# TTFT_3_0.net
KiCad netlist of a schematic drawn in Altium Designer
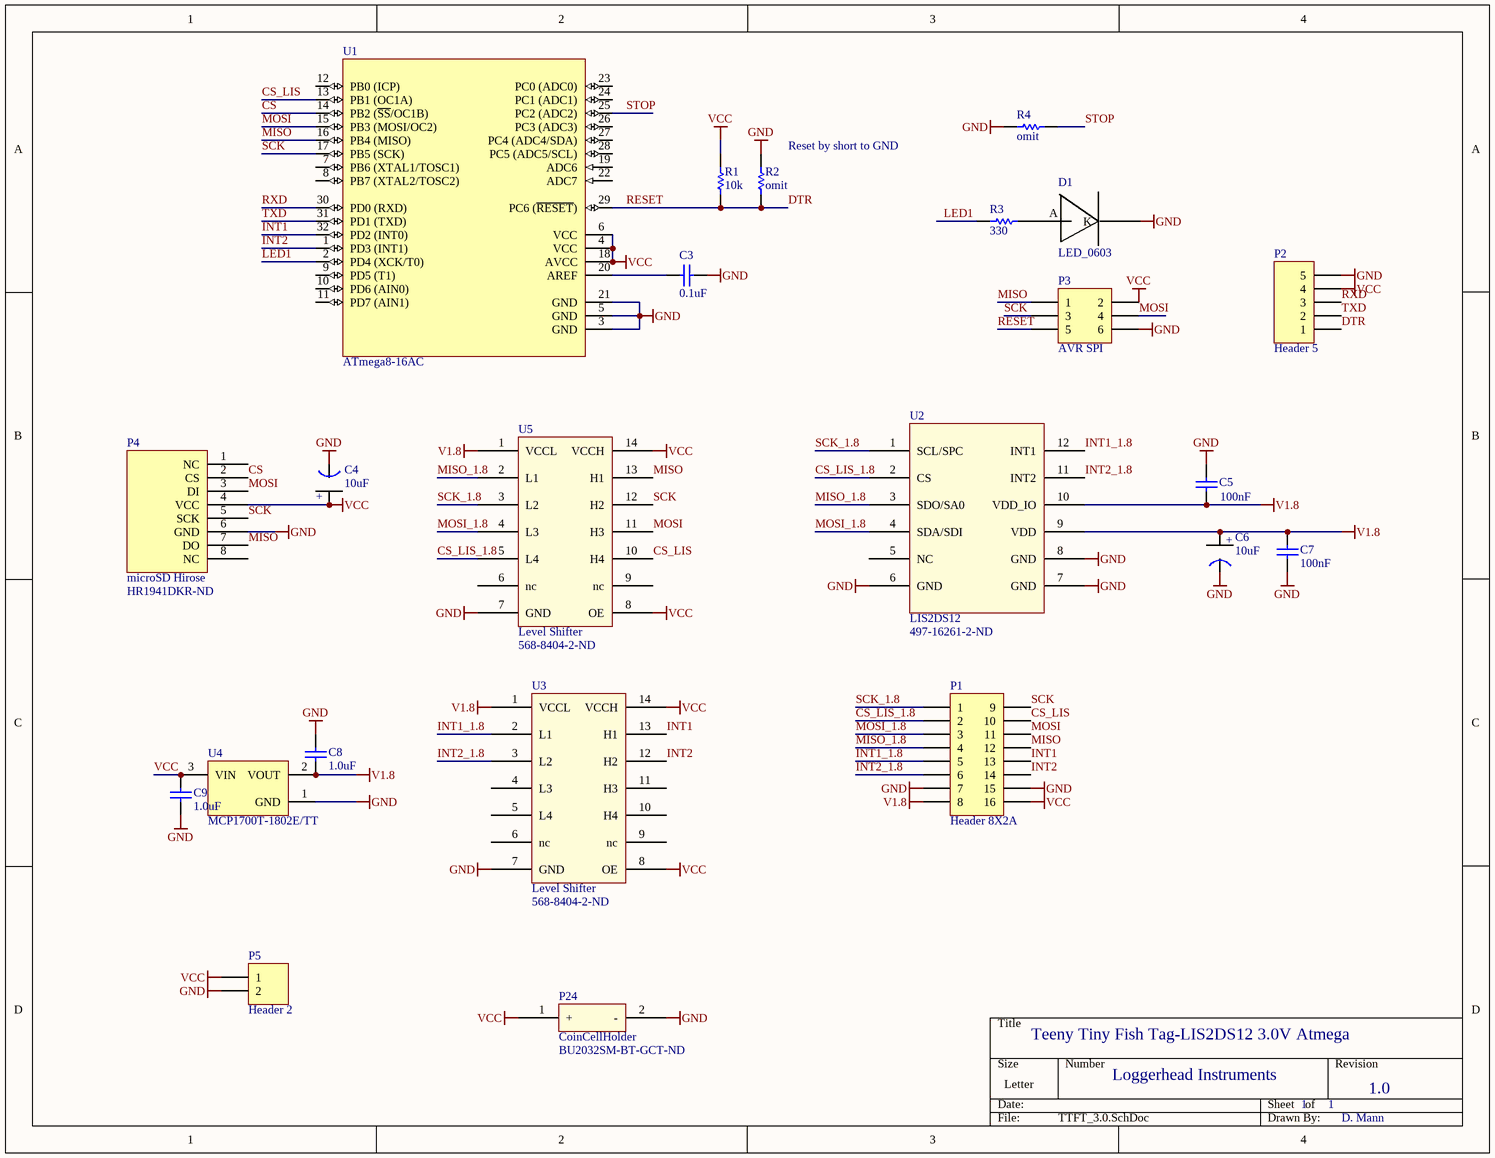
[diagram p0: TTFT_3.0.SchDoc]

(export (version "E")
  (design (tool "Eeschema 10.0.6"))
  (components
    (comp (ref "C3")
      (value "0.1uF")
      (footprint "0402")
      (description "Ceramic Chip Capacitor - Standard")
      (fields (field (name "PUBLISHER") "Altium Limited"))
      (libsource (lib "KEMET Chip Capacitor") (part "C0402"))
    )
    (comp (ref "C4") (value "10uF") (footprint "Tant0805") (libsource (lib "Loggerhead") (part "Tant0805")))
    (comp (ref "C5")
      (value "100nF")
      (footprint "0402")
      (description "Ceramic Chip Capacitor - Standard")
      (fields (field (name "PUBLISHER") "Altium Limited"))
      (libsource (lib "KEMET Chip Capacitor") (part "C0402"))
    )
    (comp (ref "C6") (value "10uF") (footprint "Tant0805") (libsource (lib "Loggerhead") (part "Tant0805")))
    (comp (ref "C7")
      (value "100nF")
      (footprint "0402")
      (description "Ceramic Chip Capacitor - Standard")
      (fields (field (name "PUBLISHER") "Altium Limited"))
      (libsource (lib "KEMET Chip Capacitor") (part "C0402"))
    )
    (comp (ref "C8")
      (value "1.0uF")
      (footprint "0402")
      (description "Ceramic Chip Capacitor - Standard")
      (fields (field (name "PUBLISHER") "Altium Limited"))
      (libsource (lib "KEMET Chip Capacitor") (part "C0402"))
    )
    (comp (ref "C9")
      (value "1.0uF")
      (footprint "0402")
      (description "Ceramic Chip Capacitor - Standard")
      (fields (field (name "PUBLISHER") "Altium Limited"))
      (libsource (lib "KEMET Chip Capacitor") (part "C0402"))
    )
    (comp (ref "D1")
      (value "LED_0603")
      (footprint "Diode0603")
      (libsource (lib "Loggerhead") (part "LED_0603"))
    )
    (comp (ref "P1")
      (value "Header 8X2A")
      (footprint "HDR2X8_CEN")
      (description "Header, 8-Pin, Dual row")
      (fields (field (name "PUBLISHER") "Altium Limited"))
      (libsource (lib "Miscellaneous Connectors") (part "Header 8X2A"))
    )
    (comp (ref "P2")
      (value "Header 5")
      (footprint "HDR1X5")
      (description "Header, 5-Pin")
      (fields (field (name "PUBLISHER") "Altium Limited"))
      (libsource (lib "Miscellaneous Connectors") (part "Header 5"))
    )
    (comp (ref "P3")
      (value "AVR SPI")
      (footprint "HDR2X3")
      (description "Header, 3-Pin, Dual row")
      (fields (field (name "PUBLISHER") "Altium Limited"))
      (libsource (lib "Miscellaneous Connectors") (part "Header 3X2"))
    )
    (comp (ref "P4")
      (value "microSD Hirose")
      (footprint "DM3D microSD")
      (fields (field (name "SUPPLIER PART NUMBER 1") "HR1941DKR-ND"))
      (libsource (lib "Loggerhead") (part "microSD Hirose"))
    )
    (comp (ref "P5")
      (value "Header 2")
      (footprint "HDR1X2")
      (description "Header, 2-Pin")
      (fields (field (name "PUBLISHER") "Altium Limited"))
      (libsource (lib "Miscellaneous Connectors") (part "Header 2"))
    )
    (comp (ref "P24")
      (value "CoinCellHolder")
      (footprint "CoinCellHolder")
      (fields (field (name "SUPPLIER PART NUMBER 1") "BU2032SM-BT-GCT-ND"))
      (libsource (lib "Loggerhead") (part "CoinCellHolder"))
    )
    (comp (ref "R1")
      (value "10k")
      (footprint "3-0603")
      (fields (field (name "PUBLISHER") "Altium Limited"))
      (libsource (lib "Panasonic Resistor") (part "ERJ3RK"))
    )
    (comp (ref "R2")
      (value "omit")
      (footprint "3-0603")
      (fields (field (name "PUBLISHER") "Altium Limited"))
      (libsource (lib "Panasonic Resistor") (part "ERJ3RK"))
    )
    (comp (ref "R3")
      (value "330")
      (footprint "3-0603")
      (fields (field (name "PUBLISHER") "Altium Limited"))
      (libsource (lib "Panasonic Resistor") (part "ERJ3RK"))
    )
    (comp (ref "R4")
      (value "omit")
      (footprint "3-0603")
      (fields (field (name "PUBLISHER") "Altium Limited"))
      (libsource (lib "Panasonic Resistor") (part "ERJ3RK"))
    )
    (comp (ref "U1")
      (value "ATmega8-16AC")
      (footprint "32M1-A_M")
      (description "8-Bit AVR Microcontroller with 8K Bytes of In-System Programmable Flash Memory")
      (fields (field (name "PUBLISHER") "Altium Limited"))
      (libsource (lib "Atmel Microcontroller 8-Bit AVR") (part "ATmega8-16AC"))
    )
    (comp (ref "U2")
      (value "LIS2DS12")
      (footprint "LGA-12")
      (fields (field (name "SUPPLIER PART NUMBER 1") "497-16261-2-ND"))
      (libsource (lib "Loggerhead") (part "LIS2DS12"))
    )
    (comp (ref "U3")
      (value "Level Shifter")
      (footprint "DHVQFN14")
      (description "Voltage level translator")
      (fields (field (name "SUPPLIER PART NUMBER 1") "568-8404-2-ND"))
      (libsource (lib "Loggerhead") (part "NTB0104"))
    )
    (comp (ref "U4")
      (value "MCP1700T-1802E/TT")
      (footprint "SOT-23-TT3_N")
      (description "Low Quiescent Current LDO, 3-Pin SOT-23, Extended Temperature, Tape and Reel")
      (fields (field (name "MANUFACTURER") "Microchip"))
      (libsource (lib "Microchip Power Management Line Regulator") (part "MCP1700T-1802E/TT"))
    )
    (comp (ref "U5")
      (value "Level Shifter")
      (footprint "DHVQFN14")
      (description "Voltage level translator")
      (fields (field (name "SUPPLIER PART NUMBER 1") "568-8404-2-ND"))
      (libsource (lib "Loggerhead") (part "NTB0104"))
    )
  )
  (nets
    (net (code "1") (name "/CS") (class "Default")
      (node (ref "P4") (pin "2") (pinfunction "CS_2") (pintype "passive"))
      (node (ref "U1") (pin "14") (pinfunction "PB2_(~{SS}/OC1B)_14") (pintype "bidirectional"))
    )
    (net (code "2") (name "/CS_LIS") (class "Default")
      (node (ref "P1") (pin "10") (pinfunction "10_10") (pintype "passive"))
      (node (ref "U1") (pin "13") (pinfunction "PB1_(OC1A)_13") (pintype "bidirectional"))
      (node (ref "U5") (pin "10") (pinfunction "H4_10") (pintype "passive"))
    )
    (net (code "3") (name "/CS_LIS_1.8") (class "Default")
      (node (ref "P1") (pin "2") (pinfunction "2_2") (pintype "passive"))
      (node (ref "U2") (pin "2") (pinfunction "CS_2") (pintype "passive"))
      (node (ref "U5") (pin "5") (pinfunction "L4_5") (pintype "passive"))
    )
    (net (code "4") (name "/DTR") (class "Default")
      (node (ref "P2") (pin "1") (pinfunction "1_1") (pintype "passive"))
      (node (ref "P3") (pin "5") (pinfunction "5_5") (pintype "passive"))
      (node (ref "R1") (pin "1") (pinfunction "1_1") (pintype "passive"))
      (node (ref "R2") (pin "1") (pinfunction "1_1") (pintype "passive"))
      (node (ref "U1") (pin "29") (pinfunction "PC6_(~{RESET})_29") (pintype "bidirectional"))
    )
    (net (code "5") (name "/INT1") (class "Default")
      (node (ref "P1") (pin "13") (pinfunction "13_13") (pintype "passive"))
      (node (ref "U1") (pin "32") (pinfunction "PD2_(INT0)_32") (pintype "bidirectional"))
      (node (ref "U3") (pin "13") (pinfunction "H1_13") (pintype "passive"))
    )
    (net (code "6") (name "/INT1_1.8") (class "Default")
      (node (ref "P1") (pin "5") (pinfunction "5_5") (pintype "passive"))
      (node (ref "U2") (pin "12") (pinfunction "INT1_12") (pintype "passive"))
      (node (ref "U3") (pin "2") (pinfunction "L1_2") (pintype "passive"))
    )
    (net (code "7") (name "/INT2") (class "Default")
      (node (ref "P1") (pin "14") (pinfunction "14_14") (pintype "passive"))
      (node (ref "U1") (pin "1") (pinfunction "PD3_(INT1)_1") (pintype "bidirectional"))
      (node (ref "U3") (pin "12") (pinfunction "H2_12") (pintype "passive"))
    )
    (net (code "8") (name "/INT2_1.8") (class "Default")
      (node (ref "P1") (pin "6") (pinfunction "6_6") (pintype "passive"))
      (node (ref "U2") (pin "11") (pinfunction "INT2_11") (pintype "passive"))
      (node (ref "U3") (pin "3") (pinfunction "L2_3") (pintype "passive"))
    )
    (net (code "9") (name "/LED1") (class "Default")
      (node (ref "R3") (pin "1") (pinfunction "1_1") (pintype "passive"))
      (node (ref "U1") (pin "2") (pinfunction "PD4_(XCK/T0)_2") (pintype "bidirectional"))
    )
    (net (code "10") (name "/MISO") (class "Default")
      (node (ref "P1") (pin "12") (pinfunction "12_12") (pintype "passive"))
      (node (ref "P3") (pin "1") (pinfunction "1_1") (pintype "passive"))
      (node (ref "P4") (pin "7") (pinfunction "DO_7") (pintype "passive"))
      (node (ref "U1") (pin "16") (pinfunction "PB4_(MISO)_16") (pintype "bidirectional"))
      (node (ref "U5") (pin "13") (pinfunction "H1_13") (pintype "passive"))
    )
    (net (code "11") (name "/MISO_1.8") (class "Default")
      (node (ref "P1") (pin "4") (pinfunction "4_4") (pintype "passive"))
      (node (ref "U2") (pin "3") (pinfunction "SDO/SA0_3") (pintype "passive"))
      (node (ref "U5") (pin "2") (pinfunction "L1_2") (pintype "passive"))
    )
    (net (code "12") (name "/MOSI") (class "Default")
      (node (ref "P1") (pin "11") (pinfunction "11_11") (pintype "passive"))
      (node (ref "P3") (pin "4") (pinfunction "4_4") (pintype "passive"))
      (node (ref "P4") (pin "3") (pinfunction "DI_3") (pintype "passive"))
      (node (ref "U1") (pin "15") (pinfunction "PB3_(MOSI/OC2)_15") (pintype "bidirectional"))
      (node (ref "U5") (pin "11") (pinfunction "H3_11") (pintype "passive"))
    )
    (net (code "13") (name "/MOSI_1.8") (class "Default")
      (node (ref "P1") (pin "3") (pinfunction "3_3") (pintype "passive"))
      (node (ref "U2") (pin "4") (pinfunction "SDA/SDI_4") (pintype "passive"))
      (node (ref "U5") (pin "4") (pinfunction "L3_4") (pintype "passive"))
    )
    (net (code "14") (name "/RXD") (class "Default")
      (node (ref "P2") (pin "3") (pinfunction "3_3") (pintype "passive"))
      (node (ref "U1") (pin "30") (pinfunction "PD0_(RXD)_30") (pintype "bidirectional"))
    )
    (net (code "15") (name "/SCK") (class "Default")
      (node (ref "P1") (pin "9") (pinfunction "9_9") (pintype "passive"))
      (node (ref "P3") (pin "3") (pinfunction "3_3") (pintype "passive"))
      (node (ref "P4") (pin "5") (pinfunction "SCK_5") (pintype "passive"))
      (node (ref "U1") (pin "17") (pinfunction "PB5_(SCK)_17") (pintype "bidirectional"))
      (node (ref "U5") (pin "12") (pinfunction "H2_12") (pintype "passive"))
    )
    (net (code "16") (name "/SCK_1.8") (class "Default")
      (node (ref "P1") (pin "1") (pinfunction "1_1") (pintype "passive"))
      (node (ref "U2") (pin "1") (pinfunction "SCL/SPC_1") (pintype "passive"))
      (node (ref "U5") (pin "3") (pinfunction "L2_3") (pintype "passive"))
    )
    (net (code "17") (name "/STOP") (class "Default")
      (node (ref "R4") (pin "1") (pinfunction "1_1") (pintype "passive"))
      (node (ref "U1") (pin "25") (pinfunction "PC2_(ADC2)_25") (pintype "bidirectional"))
    )
    (net (code "18") (name "/TXD") (class "Default")
      (node (ref "P2") (pin "2") (pinfunction "2_2") (pintype "passive"))
      (node (ref "U1") (pin "31") (pinfunction "PD1_(TXD)_31") (pintype "bidirectional"))
    )
    (net (code "19") (name "GND") (class "Default")
      (node (ref "C3") (pin "2") (pinfunction "2_2") (pintype "passive"))
      (node (ref "C4") (pin "1") (pinfunction "GND_1") (pintype "passive"))
      (node (ref "C5") (pin "2") (pinfunction "2_2") (pintype "passive"))
      (node (ref "C6") (pin "1") (pinfunction "GND_1") (pintype "passive"))
      (node (ref "C7") (pin "2") (pinfunction "2_2") (pintype "passive"))
      (node (ref "C8") (pin "2") (pinfunction "2_2") (pintype "passive"))
      (node (ref "C9") (pin "2") (pinfunction "2_2") (pintype "passive"))
      (node (ref "D1") (pin "K") (pinfunction "K_K") (pintype "passive"))
      (node (ref "P1") (pin "15") (pinfunction "15_15") (pintype "passive"))
      (node (ref "P1") (pin "7") (pinfunction "7_7") (pintype "passive"))
      (node (ref "P2") (pin "5") (pinfunction "5_5") (pintype "passive"))
      (node (ref "P24") (pin "2") (pinfunction "-_2") (pintype "passive"))
      (node (ref "P3") (pin "6") (pinfunction "6_6") (pintype "passive"))
      (node (ref "P4") (pin "6") (pinfunction "GND_6") (pintype "passive"))
      (node (ref "P5") (pin "2") (pinfunction "2_2") (pintype "passive"))
      (node (ref "R2") (pin "2") (pinfunction "2_2") (pintype "passive"))
      (node (ref "R4") (pin "2") (pinfunction "2_2") (pintype "passive"))
      (node (ref "U1") (pin "21") (pinfunction "GND_21") (pintype "power_in"))
      (node (ref "U1") (pin "3") (pinfunction "GND_3") (pintype "power_in"))
      (node (ref "U1") (pin "5") (pinfunction "GND_5") (pintype "power_in"))
      (node (ref "U2") (pin "6") (pinfunction "GND_6") (pintype "passive"))
      (node (ref "U2") (pin "7") (pinfunction "GND_7") (pintype "passive"))
      (node (ref "U2") (pin "8") (pinfunction "GND_8") (pintype "passive"))
      (node (ref "U3") (pin "7") (pinfunction "GND_7") (pintype "passive"))
      (node (ref "U4") (pin "1") (pinfunction "GND_1") (pintype "power_in"))
      (node (ref "U5") (pin "7") (pinfunction "GND_7") (pintype "passive"))
    )
    (net (code "20") (name "Net-(D1-PadA)") (class "Default")
      (node (ref "D1") (pin "A") (pinfunction "A_A") (pintype "passive"))
      (node (ref "R3") (pin "2") (pinfunction "2_2") (pintype "passive"))
    )
    (net (code "21") (name "Net-(U1-AREF)") (class "Default")
      (node (ref "C3") (pin "1") (pinfunction "1_1") (pintype "passive"))
      (node (ref "U1") (pin "20") (pinfunction "AREF_20") (pintype "passive"))
    )
    (net (code "22") (name "V1.8") (class "Default")
      (node (ref "C5") (pin "1") (pinfunction "1_1") (pintype "passive"))
      (node (ref "C6") (pin "2") (pinfunction "+_2") (pintype "passive"))
      (node (ref "C7") (pin "1") (pinfunction "1_1") (pintype "passive"))
      (node (ref "C8") (pin "1") (pinfunction "1_1") (pintype "passive"))
      (node (ref "P1") (pin "8") (pinfunction "8_8") (pintype "passive"))
      (node (ref "U2") (pin "10") (pinfunction "VDD_IO_10") (pintype "passive"))
      (node (ref "U2") (pin "9") (pinfunction "VDD_9") (pintype "passive"))
      (node (ref "U3") (pin "1") (pinfunction "VCCL_1") (pintype "passive"))
      (node (ref "U4") (pin "2") (pinfunction "VOUT_2") (pintype "power_in"))
      (node (ref "U5") (pin "1") (pinfunction "VCCL_1") (pintype "passive"))
    )
    (net (code "23") (name "VCC") (class "Default")
      (node (ref "C4") (pin "2") (pinfunction "+_2") (pintype "passive"))
      (node (ref "C9") (pin "1") (pinfunction "1_1") (pintype "passive"))
      (node (ref "P1") (pin "16") (pinfunction "16_16") (pintype "passive"))
      (node (ref "P2") (pin "4") (pinfunction "4_4") (pintype "passive"))
      (node (ref "P24") (pin "1") (pinfunction "+_1") (pintype "passive"))
      (node (ref "P3") (pin "2") (pinfunction "2_2") (pintype "passive"))
      (node (ref "P4") (pin "4") (pinfunction "VCC_4") (pintype "passive"))
      (node (ref "P5") (pin "1") (pinfunction "1_1") (pintype "passive"))
      (node (ref "R1") (pin "2") (pinfunction "2_2") (pintype "passive"))
      (node (ref "U1") (pin "18") (pinfunction "AVCC_18") (pintype "power_in"))
      (node (ref "U1") (pin "4") (pinfunction "VCC_4") (pintype "power_in"))
      (node (ref "U1") (pin "6") (pinfunction "VCC_6") (pintype "power_in"))
      (node (ref "U3") (pin "14") (pinfunction "VCCH_14") (pintype "passive"))
      (node (ref "U3") (pin "8") (pinfunction "OE_8") (pintype "passive"))
      (node (ref "U4") (pin "3") (pinfunction "VIN_3") (pintype "power_in"))
      (node (ref "U5") (pin "14") (pinfunction "VCCH_14") (pintype "passive"))
      (node (ref "U5") (pin "8") (pinfunction "OE_8") (pintype "passive"))
    )
    (net (code "24") (name "unconnected-(P4-NC-Pad1)") (class "Default")
      (node (ref "P4") (pin "1") (pinfunction "NC_1") (pintype "passive"))
    )
    (net (code "25") (name "unconnected-(P4-NC-Pad8)") (class "Default")
      (node (ref "P4") (pin "8") (pinfunction "NC_8") (pintype "passive"))
    )
    (net (code "26") (name "unconnected-(U1-ADC6-Pad19)") (class "Default")
      (node (ref "U1") (pin "19") (pinfunction "ADC6_19") (pintype "input"))
    )
    (net (code "27") (name "unconnected-(U1-ADC7-Pad22)") (class "Default")
      (node (ref "U1") (pin "22") (pinfunction "ADC7_22") (pintype "input"))
    )
    (net (code "28") (name "unconnected-(U1-PB0_(ICP)-Pad12)") (class "Default")
      (node (ref "U1") (pin "12") (pinfunction "PB0_(ICP)_12") (pintype "bidirectional"))
    )
    (net (code "29") (name "unconnected-(U1-PB6_(XTAL1{slash}TOSC1)-Pad7)") (class "Default")
      (node (ref "U1") (pin "7") (pinfunction "PB6_(XTAL1/TOSC1)_7") (pintype "bidirectional"))
    )
    (net (code "30") (name "unconnected-(U1-PB7_(XTAL2{slash}TOSC2)-Pad8)") (class "Default")
      (node (ref "U1") (pin "8") (pinfunction "PB7_(XTAL2/TOSC2)_8") (pintype "bidirectional"))
    )
    (net (code "31") (name "unconnected-(U1-PC0_(ADC0)-Pad23)") (class "Default")
      (node (ref "U1") (pin "23") (pinfunction "PC0_(ADC0)_23") (pintype "bidirectional"))
    )
    (net (code "32") (name "unconnected-(U1-PC1_(ADC1)-Pad24)") (class "Default")
      (node (ref "U1") (pin "24") (pinfunction "PC1_(ADC1)_24") (pintype "bidirectional"))
    )
    (net (code "33") (name "unconnected-(U1-PC3_(ADC3)-Pad26)") (class "Default")
      (node (ref "U1") (pin "26") (pinfunction "PC3_(ADC3)_26") (pintype "bidirectional"))
    )
    (net (code "34") (name "unconnected-(U1-PC4_(ADC4{slash}SDA)-Pad27)") (class "Default")
      (node (ref "U1") (pin "27") (pinfunction "PC4_(ADC4/SDA)_27") (pintype "bidirectional"))
    )
    (net (code "35") (name "unconnected-(U1-PC5_(ADC5{slash}SCL)-Pad28)") (class "Default")
      (node (ref "U1") (pin "28") (pinfunction "PC5_(ADC5/SCL)_28") (pintype "bidirectional"))
    )
    (net (code "36") (name "unconnected-(U1-PD5_(T1)-Pad9)") (class "Default")
      (node (ref "U1") (pin "9") (pinfunction "PD5_(T1)_9") (pintype "bidirectional"))
    )
    (net (code "37") (name "unconnected-(U1-PD6_(AIN0)-Pad10)") (class "Default")
      (node (ref "U1") (pin "10") (pinfunction "PD6_(AIN0)_10") (pintype "bidirectional"))
    )
    (net (code "38") (name "unconnected-(U1-PD7_(AIN1)-Pad11)") (class "Default")
      (node (ref "U1") (pin "11") (pinfunction "PD7_(AIN1)_11") (pintype "bidirectional"))
    )
    (net (code "39") (name "unconnected-(U2-NC-Pad5)") (class "Default")
      (node (ref "U2") (pin "5") (pinfunction "NC_5") (pintype "passive"))
    )
    (net (code "40") (name "unconnected-(U3-H3-Pad11)") (class "Default")
      (node (ref "U3") (pin "11") (pinfunction "H3_11") (pintype "passive"))
    )
    (net (code "41") (name "unconnected-(U3-H4-Pad10)") (class "Default")
      (node (ref "U3") (pin "10") (pinfunction "H4_10") (pintype "passive"))
    )
    (net (code "42") (name "unconnected-(U3-L3-Pad4)") (class "Default")
      (node (ref "U3") (pin "4") (pinfunction "L3_4") (pintype "passive"))
    )
    (net (code "43") (name "unconnected-(U3-L4-Pad5)") (class "Default")
      (node (ref "U3") (pin "5") (pinfunction "L4_5") (pintype "passive"))
    )
    (net (code "44") (name "unconnected-(U3-nc-Pad6)") (class "Default")
      (node (ref "U3") (pin "6") (pinfunction "nc_6") (pintype "passive"))
    )
    (net (code "45") (name "unconnected-(U3-nc-Pad9)") (class "Default")
      (node (ref "U3") (pin "9") (pinfunction "nc_9") (pintype "passive"))
    )
    (net (code "46") (name "unconnected-(U5-nc-Pad6)") (class "Default")
      (node (ref "U5") (pin "6") (pinfunction "nc_6") (pintype "passive"))
    )
    (net (code "47") (name "unconnected-(U5-nc-Pad9)") (class "Default")
      (node (ref "U5") (pin "9") (pinfunction "nc_9") (pintype "passive"))
    )
  )
)
